# RFLED.net
KiCad netlist of a schematic drawn in EAGLE
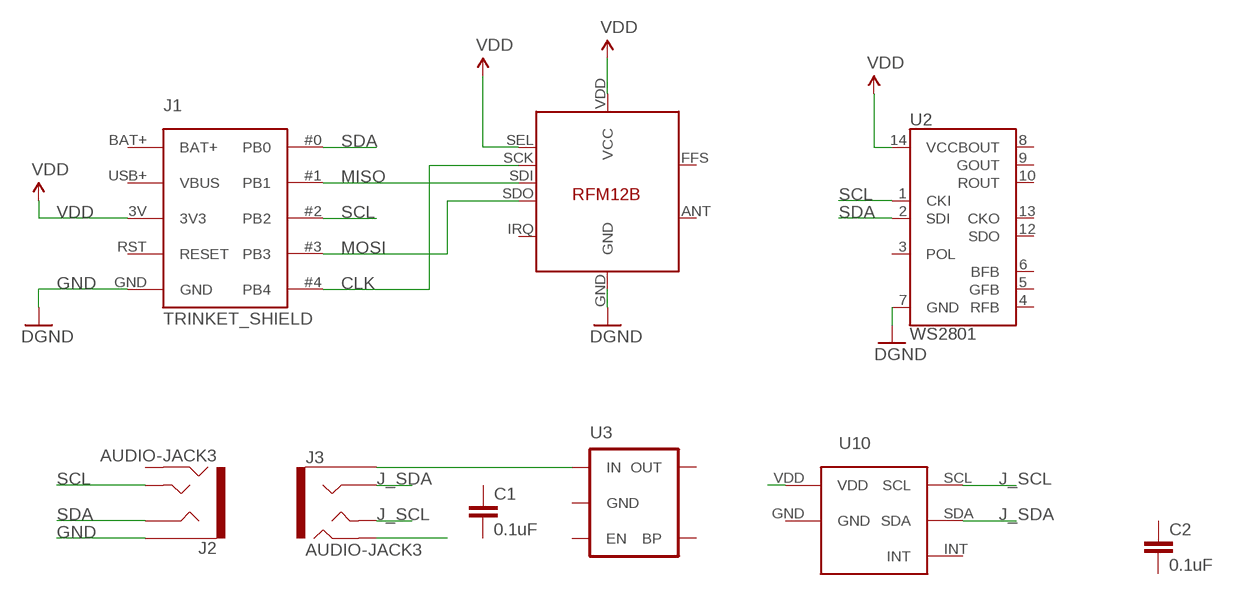
[diagram p0: schematic, sheet 1]

(export (version "E")
  (design (tool "Eeschema 10.0.6"))
  (components
    (comp (ref "C1")
      (value "0.1uF")
      (footprint "eagle-import:0603-CAP")
      (libsource (lib "eagle-import") (part "0.1UF-25V(+80/-20%)(0603)"))
    )
    (comp (ref "C2")
      (value "0.1uF")
      (footprint "eagle-import:0603-CAP")
      (libsource (lib "eagle-import") (part "0.1UF-25V(+80/-20%)(0603)"))
    )
    (comp (ref "J1")
      (value "TRINKET_SHIELD")
      (footprint "eagle-import:TRINKET_SHIELD")
      (libsource (lib "eagle-import") (part "TRINKET_SHIELD"))
    )
    (comp (ref "J2")
      (value "AUDIO-JACK3")
      (footprint "eagle-import:AUDIO-JACK-TRRS-SMD")
      (libsource (lib "eagle-import") (part "AUDIO-JACK3"))
    )
    (comp (ref "J3")
      (value "AUDIO-JACK3")
      (footprint "eagle-import:AUDIO-JACK-TRRS-SMD")
      (libsource (lib "eagle-import") (part "AUDIO-JACK3"))
    )
    (comp (ref "U1")
      (value "RFM12B")
      (footprint "eagle-import:RFM12B")
      (libsource (lib "eagle-import") (part "RFM12B"))
    )
    (comp (ref "U2")
      (value "WS2801")
      (footprint "eagle-import:SOP-14")
      (libsource (lib "eagle-import") (part "WS2801"))
    )
    (comp (ref "U3")
      (value "MIC52053.3V")
      (footprint "eagle-import:SOT23-5")
      (libsource (lib "eagle-import") (part "MIC52053.3V"))
    )
    (comp (ref "U10")
      (value "TC3472DFNL6_WIDE")
      (footprint "eagle-import:DFNL6_WIDE")
      (libsource (lib "eagle-import") (part "TC3472DFNL6_WIDE"))
    )
  )
  (nets
    (net (code "1") (name "/BAT+") (class "Default")
      (node (ref "J1") (pin "BAT+") (pinfunction "BAT+_BAT+") (pintype "power_in"))
    )
    (net (code "2") (name "/CLK") (class "Default")
      (node (ref "J1") (pin "#4") (pinfunction "PB4_#4") (pintype "bidirectional"))
      (node (ref "U1") (pin "SCK") (pinfunction "SCK_SCK") (pintype "input"))
    )
    (net (code "3") (name "/J_SCL") (class "Default")
      (node (ref "J3") (pin "TIP") (pinfunction "TIP_TIP") (pintype "bidirectional"))
      (node (ref "U10") (pin "SCL") (pinfunction "SCL_SCL") (pintype "bidirectional"))
    )
    (net (code "4") (name "/J_SDA") (class "Default")
      (node (ref "J3") (pin "RING1") (pinfunction "RING1_RING1") (pintype "bidirectional"))
      (node (ref "U10") (pin "SDA") (pinfunction "SDA_SDA") (pintype "bidirectional"))
    )
    (net (code "5") (name "/MISO") (class "Default")
      (node (ref "J1") (pin "#1") (pinfunction "PB1_#1") (pintype "bidirectional"))
      (node (ref "U1") (pin "SDI") (pinfunction "SDI_SDI") (pintype "input"))
    )
    (net (code "6") (name "/MOSI") (class "Default")
      (node (ref "J1") (pin "#3") (pinfunction "PB3_#3") (pintype "bidirectional"))
      (node (ref "U1") (pin "SDO") (pinfunction "SDO_SDO") (pintype "output"))
    )
    (net (code "7") (name "/SCL") (class "Default")
      (node (ref "J1") (pin "#2") (pinfunction "PB2_#2") (pintype "bidirectional"))
      (node (ref "J2") (pin "TIP") (pinfunction "TIP_TIP") (pintype "bidirectional"))
      (node (ref "U2") (pin "1") (pinfunction "CKI_1") (pintype "bidirectional"))
    )
    (net (code "8") (name "/SDA") (class "Default")
      (node (ref "J1") (pin "#0") (pinfunction "PB0_#0") (pintype "bidirectional"))
      (node (ref "J2") (pin "RING1") (pinfunction "RING1_RING1") (pintype "bidirectional"))
      (node (ref "U2") (pin "2") (pinfunction "SDI_2") (pintype "bidirectional"))
    )
    (net (code "9") (name "/VBUS") (class "Default")
      (node (ref "J1") (pin "USB+") (pinfunction "VBUS_USB+") (pintype "power_in"))
    )
    (net (code "10") (name "DGND") (class "Default")
      (node (ref "J1") (pin "GND") (pinfunction "GND_GND") (pintype "bidirectional"))
      (node (ref "J2") (pin "EARTH") (pinfunction "EARTH_EARTH") (pintype "bidirectional"))
      (node (ref "U1") (pin "GND") (pinfunction "GND_GND") (pintype "power_in"))
      (node (ref "U2") (pin "7") (pinfunction "GND_7") (pintype "bidirectional"))
    )
    (net (code "11") (name "Net-(U3-IN)") (class "Default")
      (node (ref "J3") (pin "EARTH") (pinfunction "EARTH_EARTH") (pintype "bidirectional"))
      (node (ref "U3") (pin "1") (pinfunction "IN_1") (pintype "input"))
    )
    (net (code "12") (name "VDD") (class "Default")
      (node (ref "J1") (pin "3V") (pinfunction "3V3_3V") (pintype "power_in"))
      (node (ref "U1") (pin "SEL") (pinfunction "SEL_SEL") (pintype "input"))
      (node (ref "U1") (pin "VDD") (pinfunction "VCC_VDD") (pintype "power_in"))
      (node (ref "U2") (pin "14") (pinfunction "VCC_14") (pintype "bidirectional"))
    )
    (net (code "13") (name "unconnected-(C1-Pad1)") (class "Default")
      (node (ref "C1") (pin "1") (pinfunction "1_1") (pintype "passive"))
    )
    (net (code "14") (name "unconnected-(C1-Pad2)") (class "Default")
      (node (ref "C1") (pin "2") (pinfunction "2_2") (pintype "passive"))
    )
    (net (code "15") (name "unconnected-(C2-Pad1)") (class "Default")
      (node (ref "C2") (pin "1") (pinfunction "1_1") (pintype "passive"))
    )
    (net (code "16") (name "unconnected-(C2-Pad2)") (class "Default")
      (node (ref "C2") (pin "2") (pinfunction "2_2") (pintype "passive"))
    )
    (net (code "17") (name "unconnected-(J1-RESET-PadRST)") (class "Default")
      (node (ref "J1") (pin "RST") (pinfunction "RESET_RST") (pintype "bidirectional"))
    )
    (net (code "18") (name "unconnected-(J2-PadRING2)") (class "Default")
      (node (ref "J2") (pin "RING2") (pinfunction "RING2_RING2") (pintype "bidirectional"))
    )
    (net (code "19") (name "unconnected-(J3-PadRING2)") (class "Default")
      (node (ref "J3") (pin "RING2") (pinfunction "RING2_RING2") (pintype "bidirectional"))
    )
    (net (code "20") (name "unconnected-(U1-PadANT)") (class "Default")
      (node (ref "U1") (pin "ANT") (pinfunction "ANT_ANT") (pintype "passive"))
    )
    (net (code "21") (name "unconnected-(U1-PadFFS)") (class "Default")
      (node (ref "U1") (pin "FFS") (pinfunction "FFS_FFS") (pintype "bidirectional"))
    )
    (net (code "22") (name "unconnected-(U1-PadIRQ)") (class "Default")
      (node (ref "U1") (pin "IRQ") (pinfunction "IRQ_IRQ") (pintype "open_collector"))
    )
    (net (code "23") (name "unconnected-(U2-BFB-Pad6)") (class "Default")
      (node (ref "U2") (pin "6") (pinfunction "BFB_6") (pintype "bidirectional"))
    )
    (net (code "24") (name "unconnected-(U2-BOUT-Pad8)") (class "Default")
      (node (ref "U2") (pin "8") (pinfunction "BOUT_8") (pintype "bidirectional"))
    )
    (net (code "25") (name "unconnected-(U2-CKO-Pad13)") (class "Default")
      (node (ref "U2") (pin "13") (pinfunction "CKO_13") (pintype "bidirectional"))
    )
    (net (code "26") (name "unconnected-(U2-GFB-Pad5)") (class "Default")
      (node (ref "U2") (pin "5") (pinfunction "GFB_5") (pintype "bidirectional"))
    )
    (net (code "27") (name "unconnected-(U2-GOUT-Pad9)") (class "Default")
      (node (ref "U2") (pin "9") (pinfunction "GOUT_9") (pintype "bidirectional"))
    )
    (net (code "28") (name "unconnected-(U2-POL-Pad3)") (class "Default")
      (node (ref "U2") (pin "3") (pinfunction "POL_3") (pintype "bidirectional"))
    )
    (net (code "29") (name "unconnected-(U2-RFB-Pad4)") (class "Default")
      (node (ref "U2") (pin "4") (pinfunction "RFB_4") (pintype "bidirectional"))
    )
    (net (code "30") (name "unconnected-(U2-ROUT-Pad10)") (class "Default")
      (node (ref "U2") (pin "10") (pinfunction "ROUT_10") (pintype "bidirectional"))
    )
    (net (code "31") (name "unconnected-(U2-SDO-Pad12)") (class "Default")
      (node (ref "U2") (pin "12") (pinfunction "SDO_12") (pintype "bidirectional"))
    )
    (net (code "32") (name "unconnected-(U3-BP-Pad4)") (class "Default")
      (node (ref "U3") (pin "4") (pinfunction "BP_4") (pintype "input"))
    )
    (net (code "33") (name "unconnected-(U3-EN-Pad3)") (class "Default")
      (node (ref "U3") (pin "3") (pinfunction "EN_3") (pintype "input"))
    )
    (net (code "34") (name "unconnected-(U3-GND-Pad2)") (class "Default")
      (node (ref "U3") (pin "2") (pinfunction "GND_2") (pintype "input"))
    )
    (net (code "35") (name "unconnected-(U3-OUT-Pad5)") (class "Default")
      (node (ref "U3") (pin "5") (pinfunction "OUT_5") (pintype "passive"))
    )
    (net (code "36") (name "unconnected-(U10-PadGND)") (class "Default")
      (node (ref "U10") (pin "GND") (pinfunction "GND_GND") (pintype "bidirectional"))
    )
    (net (code "37") (name "unconnected-(U10-PadINT)") (class "Default")
      (node (ref "U10") (pin "INT") (pinfunction "INT_INT") (pintype "bidirectional"))
    )
    (net (code "38") (name "unconnected-(U10-PadVDD)") (class "Default")
      (node (ref "U10") (pin "VDD") (pinfunction "VDD_VDD") (pintype "bidirectional"))
    )
  )
)
